# GSM_-_BGS2.net
KiCad netlist of a schematic drawn in Altium Designer
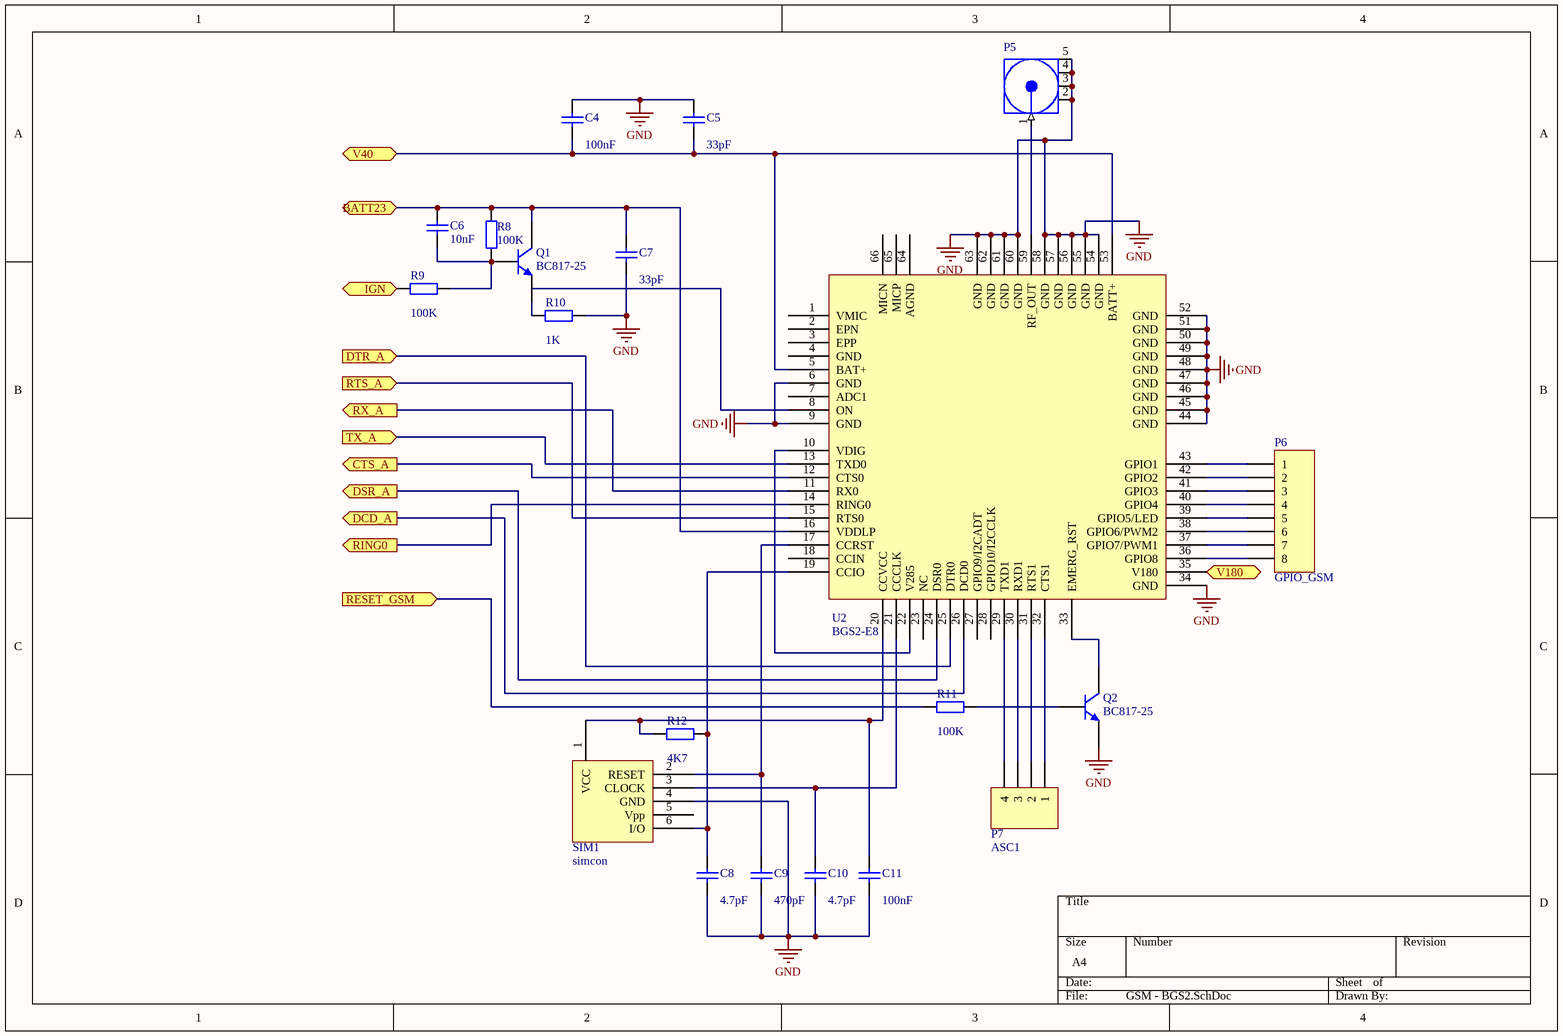
[diagram p0: GSM - BGS2.SchDoc]

(export (version "E")
  (design (tool "Eeschema 10.0.6"))
  (components
    (comp (ref "C4")
      (value "100nF")
      (footprint "RAD-0.1")
      (description "Capacitor")
      (fields (field (name "Comment") "Cap") (field (name "PUBLISHER") "Altium Limited"))
      (libsource (lib "Miscellaneous Devices") (part "Cap"))
    )
    (comp (ref "C5")
      (value "33pF")
      (footprint "RAD-0.1")
      (description "Capacitor")
      (fields (field (name "Comment") "Cap") (field (name "PUBLISHER") "Altium Limited"))
      (libsource (lib "Miscellaneous Devices") (part "Cap"))
    )
    (comp (ref "C6")
      (value "10nF")
      (footprint "RAD-0.1")
      (description "Capacitor")
      (fields (field (name "Comment") "Cap") (field (name "PUBLISHER") "Altium Limited"))
      (libsource (lib "Miscellaneous Devices") (part "Cap"))
    )
    (comp (ref "C7")
      (value "33pF")
      (footprint "RAD-0.1")
      (description "Capacitor")
      (fields (field (name "Comment") "Cap") (field (name "PUBLISHER") "Altium Limited"))
      (libsource (lib "Miscellaneous Devices") (part "Cap"))
    )
    (comp (ref "C8")
      (value "4.7pF")
      (footprint "RAD-0.1")
      (description "Capacitor")
      (fields (field (name "Comment") "Cap") (field (name "PUBLISHER") "Altium Limited"))
      (libsource (lib "Miscellaneous Devices") (part "Cap"))
    )
    (comp (ref "C9")
      (value "470pF")
      (footprint "RAD-0.1")
      (description "Capacitor")
      (fields (field (name "Comment") "Cap") (field (name "PUBLISHER") "Altium Limited"))
      (libsource (lib "Miscellaneous Devices") (part "Cap"))
    )
    (comp (ref "C10")
      (value "4.7pF")
      (footprint "RAD-0.1")
      (description "Capacitor")
      (fields (field (name "Comment") "Cap") (field (name "PUBLISHER") "Altium Limited"))
      (libsource (lib "Miscellaneous Devices") (part "Cap"))
    )
    (comp (ref "C11")
      (value "100nF")
      (footprint "RAD-0.1")
      (description "Capacitor")
      (fields (field (name "Comment") "Cap") (field (name "PUBLISHER") "Altium Limited"))
      (libsource (lib "Miscellaneous Devices") (part "Cap"))
    )
    (comp (ref "P5")
      (value "COAX-M")
      (footprint "MCX5.08-H5")
      (description "RF Coaxial PCB Connector, MMCX; Thru-Hole, Vertical Mount Plug,  50 Ohm Impedance")
      (fields (field (name "PUBLISHER") "Altium Limited"))
      (libsource (lib "Miscellaneous Connectors") (part "COAX-M"))
    )
    (comp (ref "P6")
      (value "GPIO_GSM")
      (footprint "HDR1X8H")
      (description "Header, 8-Pin, Right Angle")
      (fields (field (name "PUBLISHER") "Altium Limited"))
      (libsource (lib "Miscellaneous Connectors") (part "Header 8H"))
    )
    (comp (ref "P7")
      (value "ASC1")
      (footprint "HDR1X4H")
      (description "Header, 4-Pin, Right Angle")
      (fields (field (name "PUBLISHER") "Altium Limited"))
      (libsource (lib "Miscellaneous Connectors") (part "Header 4H"))
    )
    (comp (ref "Q1")
      (value "BC817-25")
      (footprint "SOT-23A")
      (description "NPN General Purpose Amplifier")
      (fields (field (name "PUBLISHER") "Altium Limited"))
      (libsource (lib "FSC Discrete BJT") (part "BC817-25"))
    )
    (comp (ref "Q2")
      (value "BC817-25")
      (footprint "SOT-23A")
      (description "NPN General Purpose Amplifier")
      (fields (field (name "PUBLISHER") "Altium Limited"))
      (libsource (lib "FSC Discrete BJT") (part "BC817-25"))
    )
    (comp (ref "R8")
      (value "100K")
      (footprint "AXIAL-0.4")
      (description "Resistor")
      (fields (field (name "Comment") "Res2") (field (name "PUBLISHER") "Altium Limited"))
      (libsource (lib "") (part "Res2_1"))
    )
    (comp (ref "R9")
      (value "100K")
      (footprint "AXIAL-0.4")
      (description "Resistor")
      (fields (field (name "Comment") "Res2") (field (name "PUBLISHER") "Altium Limited"))
      (libsource (lib "Miscellaneous Devices") (part "Res2"))
    )
    (comp (ref "R10")
      (value "1K")
      (footprint "AXIAL-0.4")
      (description "Resistor")
      (fields (field (name "Comment") "Res2") (field (name "PUBLISHER") "Altium Limited"))
      (libsource (lib "") (part "Res2_1"))
    )
    (comp (ref "R11")
      (value "100K")
      (footprint "AXIAL-0.4")
      (description "Resistor")
      (fields (field (name "Comment") "Res2") (field (name "PUBLISHER") "Altium Limited"))
      (libsource (lib "") (part "Res2_1"))
    )
    (comp (ref "R12")
      (value "4K7")
      (footprint "AXIAL-0.4")
      (description "Resistor")
      (fields (field (name "Comment") "Res2") (field (name "PUBLISHER") "Altium Limited"))
      (libsource (lib "") (part "Res2_1"))
    )
    (comp (ref "SIM1") (value "simcon") (footprint "SIMCON-6pin") (libsource (lib "gps&gsm") (part "simcon")))
    (comp (ref "U2")
      (value "BGS2-E8")
      (footprint "QFN120P2700X1820X270-66M")
      (libsource (lib "gps&gsm") (part "BGS2-E8"))
    )
  )
  (nets
    (net (code "1") (name "/BATT23") (class "Default")
      (node (ref "C6") (pin "2") (pinfunction "2_2") (pintype "passive"))
      (node (ref "C7") (pin "1") (pinfunction "1_1") (pintype "passive"))
      (node (ref "Q1") (pin "3") (pinfunction "C_3") (pintype "passive"))
      (node (ref "R8") (pin "2") (pinfunction "2_2") (pintype "passive"))
      (node (ref "U2") (pin "16") (pinfunction "VDDLP_16") (pintype "passive"))
    )
    (net (code "2") (name "/CTS_A") (class "Default")
      (node (ref "U2") (pin "12") (pinfunction "CTS0_12") (pintype "passive"))
    )
    (net (code "3") (name "/DCD_A") (class "Default")
      (node (ref "U2") (pin "26") (pinfunction "DCD0_26") (pintype "passive"))
    )
    (net (code "4") (name "/DSR_A") (class "Default")
      (node (ref "U2") (pin "24") (pinfunction "DSR0_24") (pintype "passive"))
    )
    (net (code "5") (name "/DTR_A") (class "Default")
      (node (ref "U2") (pin "25") (pinfunction "DTR0_25") (pintype "passive"))
    )
    (net (code "6") (name "/IGN") (class "Default")
      (node (ref "R9") (pin "1") (pinfunction "1_1") (pintype "passive"))
    )
    (net (code "7") (name "/RESET_GSM") (class "Default")
      (node (ref "R11") (pin "1") (pinfunction "1_1") (pintype "passive"))
    )
    (net (code "8") (name "/RING0") (class "Default")
      (node (ref "U2") (pin "14") (pinfunction "RING0_14") (pintype "passive"))
    )
    (net (code "9") (name "/RTS_A") (class "Default")
      (node (ref "U2") (pin "15") (pinfunction "RTS0_15") (pintype "passive"))
    )
    (net (code "10") (name "/RX_A") (class "Default")
      (node (ref "U2") (pin "11") (pinfunction "RX0_11") (pintype "passive"))
    )
    (net (code "11") (name "/TX_A") (class "Default")
      (node (ref "U2") (pin "13") (pinfunction "TXD0_13") (pintype "passive"))
    )
    (net (code "12") (name "/V40") (class "Default")
      (node (ref "C4") (pin "1") (pinfunction "1_1") (pintype "passive"))
      (node (ref "C5") (pin "1") (pinfunction "1_1") (pintype "passive"))
      (node (ref "U2") (pin "5") (pinfunction "BAT+_5") (pintype "passive"))
      (node (ref "U2") (pin "53") (pinfunction "BATT+_53") (pintype "passive"))
    )
    (net (code "13") (name "/V180") (class "Default")
      (node (ref "U2") (pin "35") (pinfunction "V180_35") (pintype "passive"))
    )
    (net (code "14") (name "GND") (class "Default")
      (node (ref "C10") (pin "1") (pinfunction "1_1") (pintype "passive"))
      (node (ref "C11") (pin "1") (pinfunction "1_1") (pintype "passive"))
      (node (ref "C4") (pin "2") (pinfunction "2_2") (pintype "passive"))
      (node (ref "C5") (pin "2") (pinfunction "2_2") (pintype "passive"))
      (node (ref "C7") (pin "2") (pinfunction "2_2") (pintype "passive"))
      (node (ref "C8") (pin "1") (pinfunction "1_1") (pintype "passive"))
      (node (ref "C9") (pin "1") (pinfunction "1_1") (pintype "passive"))
      (node (ref "P5") (pin "2") (pinfunction "GND_2") (pintype "power_in"))
      (node (ref "P5") (pin "3") (pinfunction "GND_3") (pintype "power_in"))
      (node (ref "P5") (pin "4") (pinfunction "GND_4") (pintype "power_in"))
      (node (ref "P5") (pin "5") (pinfunction "GND_5") (pintype "power_in"))
      (node (ref "Q2") (pin "2") (pinfunction "E_2") (pintype "passive"))
      (node (ref "R10") (pin "2") (pinfunction "2_2") (pintype "passive"))
      (node (ref "SIM1") (pin "4") (pinfunction "GND_4") (pintype "passive"))
      (node (ref "U2") (pin "34") (pinfunction "GND_34") (pintype "passive"))
      (node (ref "U2") (pin "44") (pinfunction "GND_44") (pintype "passive"))
      (node (ref "U2") (pin "45") (pinfunction "GND_45") (pintype "passive"))
      (node (ref "U2") (pin "46") (pinfunction "GND_46") (pintype "passive"))
      (node (ref "U2") (pin "47") (pinfunction "GND_47") (pintype "passive"))
      (node (ref "U2") (pin "48") (pinfunction "GND_48") (pintype "passive"))
      (node (ref "U2") (pin "49") (pinfunction "GND_49") (pintype "passive"))
      (node (ref "U2") (pin "50") (pinfunction "GND_50") (pintype "passive"))
      (node (ref "U2") (pin "51") (pinfunction "GND_51") (pintype "passive"))
      (node (ref "U2") (pin "52") (pinfunction "GND_52") (pintype "passive"))
      (node (ref "U2") (pin "54") (pinfunction "GND_54") (pintype "passive"))
      (node (ref "U2") (pin "55") (pinfunction "GND_55") (pintype "passive"))
      (node (ref "U2") (pin "56") (pinfunction "GND_56") (pintype "passive"))
      (node (ref "U2") (pin "57") (pinfunction "GND_57") (pintype "passive"))
      (node (ref "U2") (pin "58") (pinfunction "GND_58") (pintype "passive"))
      (node (ref "U2") (pin "6") (pinfunction "GND_6") (pintype "passive"))
      (node (ref "U2") (pin "60") (pinfunction "GND_60") (pintype "passive"))
      (node (ref "U2") (pin "61") (pinfunction "GND_61") (pintype "passive"))
      (node (ref "U2") (pin "62") (pinfunction "GND_62") (pintype "passive"))
      (node (ref "U2") (pin "63") (pinfunction "GND_63") (pintype "passive"))
      (node (ref "U2") (pin "9") (pinfunction "GND_9") (pintype "passive"))
    )
    (net (code "15") (name "Net-(P5-Signal)") (class "Default")
      (node (ref "P5") (pin "1") (pinfunction "Signal_1") (pintype "input"))
      (node (ref "U2") (pin "59") (pinfunction "RF_OUT_59") (pintype "passive"))
    )
    (net (code "16") (name "Net-(Q1-B)") (class "Default")
      (node (ref "C6") (pin "1") (pinfunction "1_1") (pintype "passive"))
      (node (ref "Q1") (pin "1") (pinfunction "B_1") (pintype "passive"))
      (node (ref "R8") (pin "1") (pinfunction "1_1") (pintype "passive"))
      (node (ref "R9") (pin "2") (pinfunction "2_2") (pintype "passive"))
    )
    (net (code "17") (name "Net-(Q1-E)") (class "Default")
      (node (ref "Q1") (pin "2") (pinfunction "E_2") (pintype "passive"))
      (node (ref "R10") (pin "1") (pinfunction "1_1") (pintype "passive"))
    )
    (net (code "18") (name "Net-(Q2-B)") (class "Default")
      (node (ref "Q2") (pin "1") (pinfunction "B_1") (pintype "passive"))
      (node (ref "R11") (pin "2") (pinfunction "2_2") (pintype "passive"))
    )
    (net (code "19") (name "Net-(Q2-C)") (class "Default")
      (node (ref "Q2") (pin "3") (pinfunction "C_3") (pintype "passive"))
      (node (ref "U2") (pin "33") (pinfunction "EMERG_RST_33") (pintype "passive"))
    )
    (net (code "20") (name "Net-(SIM1-CLOCK)") (class "Default")
      (node (ref "C10") (pin "2") (pinfunction "2_2") (pintype "passive"))
      (node (ref "SIM1") (pin "3") (pinfunction "CLOCK_3") (pintype "passive"))
      (node (ref "U2") (pin "21") (pinfunction "CCCLK_21") (pintype "passive"))
    )
    (net (code "21") (name "Net-(SIM1-I{slash}O)") (class "Default")
      (node (ref "C8") (pin "2") (pinfunction "2_2") (pintype "passive"))
      (node (ref "R12") (pin "2") (pinfunction "2_2") (pintype "passive"))
      (node (ref "SIM1") (pin "6") (pinfunction "I/O_6") (pintype "passive"))
      (node (ref "U2") (pin "19") (pinfunction "CCIO_19") (pintype "passive"))
    )
    (net (code "22") (name "Net-(SIM1-RESET)") (class "Default")
      (node (ref "C9") (pin "2") (pinfunction "2_2") (pintype "passive"))
      (node (ref "SIM1") (pin "2") (pinfunction "RESET_2") (pintype "passive"))
      (node (ref "U2") (pin "17") (pinfunction "CCRST_17") (pintype "passive"))
    )
    (net (code "23") (name "Net-(SIM1-VCC)") (class "Default")
      (node (ref "C11") (pin "2") (pinfunction "2_2") (pintype "passive"))
      (node (ref "R12") (pin "1") (pinfunction "1_1") (pintype "passive"))
      (node (ref "SIM1") (pin "1") (pinfunction "VCC_1") (pintype "passive"))
      (node (ref "U2") (pin "20") (pinfunction "CCVCC_20") (pintype "passive"))
    )
    (net (code "24") (name "Net-(U2-CTS1)") (class "Default")
      (node (ref "P7") (pin "1") (pinfunction "1_1") (pintype "passive"))
      (node (ref "U2") (pin "32") (pinfunction "CTS1_32") (pintype "passive"))
    )
    (net (code "25") (name "Net-(U2-GPIO1)") (class "Default")
      (node (ref "P6") (pin "1") (pinfunction "1_1") (pintype "passive"))
      (node (ref "U2") (pin "43") (pinfunction "GPIO1_43") (pintype "passive"))
    )
    (net (code "26") (name "Net-(U2-GPIO2)") (class "Default")
      (node (ref "P6") (pin "2") (pinfunction "2_2") (pintype "passive"))
      (node (ref "U2") (pin "42") (pinfunction "GPIO2_42") (pintype "passive"))
    )
    (net (code "27") (name "Net-(U2-GPIO3)") (class "Default")
      (node (ref "P6") (pin "3") (pinfunction "3_3") (pintype "passive"))
      (node (ref "U2") (pin "41") (pinfunction "GPIO3_41") (pintype "passive"))
    )
    (net (code "28") (name "Net-(U2-GPIO4)") (class "Default")
      (node (ref "P6") (pin "4") (pinfunction "4_4") (pintype "passive"))
      (node (ref "U2") (pin "40") (pinfunction "GPIO4_40") (pintype "passive"))
    )
    (net (code "29") (name "Net-(U2-GPIO5{slash}LED)") (class "Default")
      (node (ref "P6") (pin "5") (pinfunction "5_5") (pintype "passive"))
      (node (ref "U2") (pin "39") (pinfunction "GPIO5/LED_39") (pintype "passive"))
    )
    (net (code "30") (name "Net-(U2-GPIO6{slash}PWM2)") (class "Default")
      (node (ref "P6") (pin "6") (pinfunction "6_6") (pintype "passive"))
      (node (ref "U2") (pin "38") (pinfunction "GPIO6/PWM2_38") (pintype "passive"))
    )
    (net (code "31") (name "Net-(U2-GPIO7{slash}PWM1)") (class "Default")
      (node (ref "P6") (pin "7") (pinfunction "7_7") (pintype "passive"))
      (node (ref "U2") (pin "37") (pinfunction "GPIO7/PWM1_37") (pintype "passive"))
    )
    (net (code "32") (name "Net-(U2-GPIO8)") (class "Default")
      (node (ref "P6") (pin "8") (pinfunction "8_8") (pintype "passive"))
      (node (ref "U2") (pin "36") (pinfunction "GPIO8_36") (pintype "passive"))
    )
    (net (code "33") (name "Net-(U2-RTS1)") (class "Default")
      (node (ref "P7") (pin "2") (pinfunction "2_2") (pintype "passive"))
      (node (ref "U2") (pin "31") (pinfunction "RTS1_31") (pintype "passive"))
    )
    (net (code "34") (name "Net-(U2-RXD1)") (class "Default")
      (node (ref "P7") (pin "3") (pinfunction "3_3") (pintype "passive"))
      (node (ref "U2") (pin "30") (pinfunction "RXD1_30") (pintype "passive"))
    )
    (net (code "35") (name "Net-(U2-TXD1)") (class "Default")
      (node (ref "P7") (pin "4") (pinfunction "4_4") (pintype "passive"))
      (node (ref "U2") (pin "29") (pinfunction "TXD1_29") (pintype "passive"))
    )
    (net (code "36") (name "Net-(U2-V285)") (class "Default")
      (node (ref "U2") (pin "10") (pinfunction "VDIG_10") (pintype "passive"))
      (node (ref "U2") (pin "22") (pinfunction "V285_22") (pintype "passive"))
    )
    (net (code "37") (name "unconnected-(SIM1-Vpp-Pad5)") (class "Default")
      (node (ref "SIM1") (pin "5") (pinfunction "Vpp_5") (pintype "passive"))
    )
    (net (code "38") (name "unconnected-(U2-ADC1-Pad7)") (class "Default")
      (node (ref "U2") (pin "7") (pinfunction "ADC1_7") (pintype "passive"))
    )
    (net (code "39") (name "unconnected-(U2-AGND-Pad64)") (class "Default")
      (node (ref "U2") (pin "64") (pinfunction "AGND_64") (pintype "passive"))
    )
    (net (code "40") (name "unconnected-(U2-CCIN-Pad18)") (class "Default")
      (node (ref "U2") (pin "18") (pinfunction "CCIN_18") (pintype "passive"))
    )
    (net (code "41") (name "unconnected-(U2-EPN-Pad2)") (class "Default")
      (node (ref "U2") (pin "2") (pinfunction "EPN_2") (pintype "passive"))
    )
    (net (code "42") (name "unconnected-(U2-EPP-Pad3)") (class "Default")
      (node (ref "U2") (pin "3") (pinfunction "EPP_3") (pintype "passive"))
    )
    (net (code "43") (name "unconnected-(U2-GND-Pad4)") (class "Default")
      (node (ref "U2") (pin "4") (pinfunction "GND_4") (pintype "passive"))
    )
    (net (code "44") (name "unconnected-(U2-GPIO9{slash}I2CADT-Pad27)") (class "Default")
      (node (ref "U2") (pin "27") (pinfunction "GPIO9/I2CADT_27") (pintype "passive"))
    )
    (net (code "45") (name "unconnected-(U2-GPIO10{slash}I2CCLK-Pad28)") (class "Default")
      (node (ref "U2") (pin "28") (pinfunction "GPIO10/I2CCLK_28") (pintype "passive"))
    )
    (net (code "46") (name "unconnected-(U2-MICN-Pad66)") (class "Default")
      (node (ref "U2") (pin "66") (pinfunction "MICN_66") (pintype "passive"))
    )
    (net (code "47") (name "unconnected-(U2-MICP-Pad65)") (class "Default")
      (node (ref "U2") (pin "65") (pinfunction "MICP_65") (pintype "passive"))
    )
    (net (code "48") (name "unconnected-(U2-NC-Pad23)") (class "Default")
      (node (ref "U2") (pin "23") (pinfunction "NC_23") (pintype "passive"))
    )
    (net (code "49") (name "unconnected-(U2-ON-Pad8)") (class "Default")
      (node (ref "U2") (pin "8") (pinfunction "ON_8") (pintype "passive"))
    )
    (net (code "50") (name "unconnected-(U2-VMIC-Pad1)") (class "Default")
      (node (ref "U2") (pin "1") (pinfunction "VMIC_1") (pintype "passive"))
    )
  )
)
